# SCH_ZX-WiFi_2024-03-22.net
KiCad netlist of a schematic drawn in EasyEDA
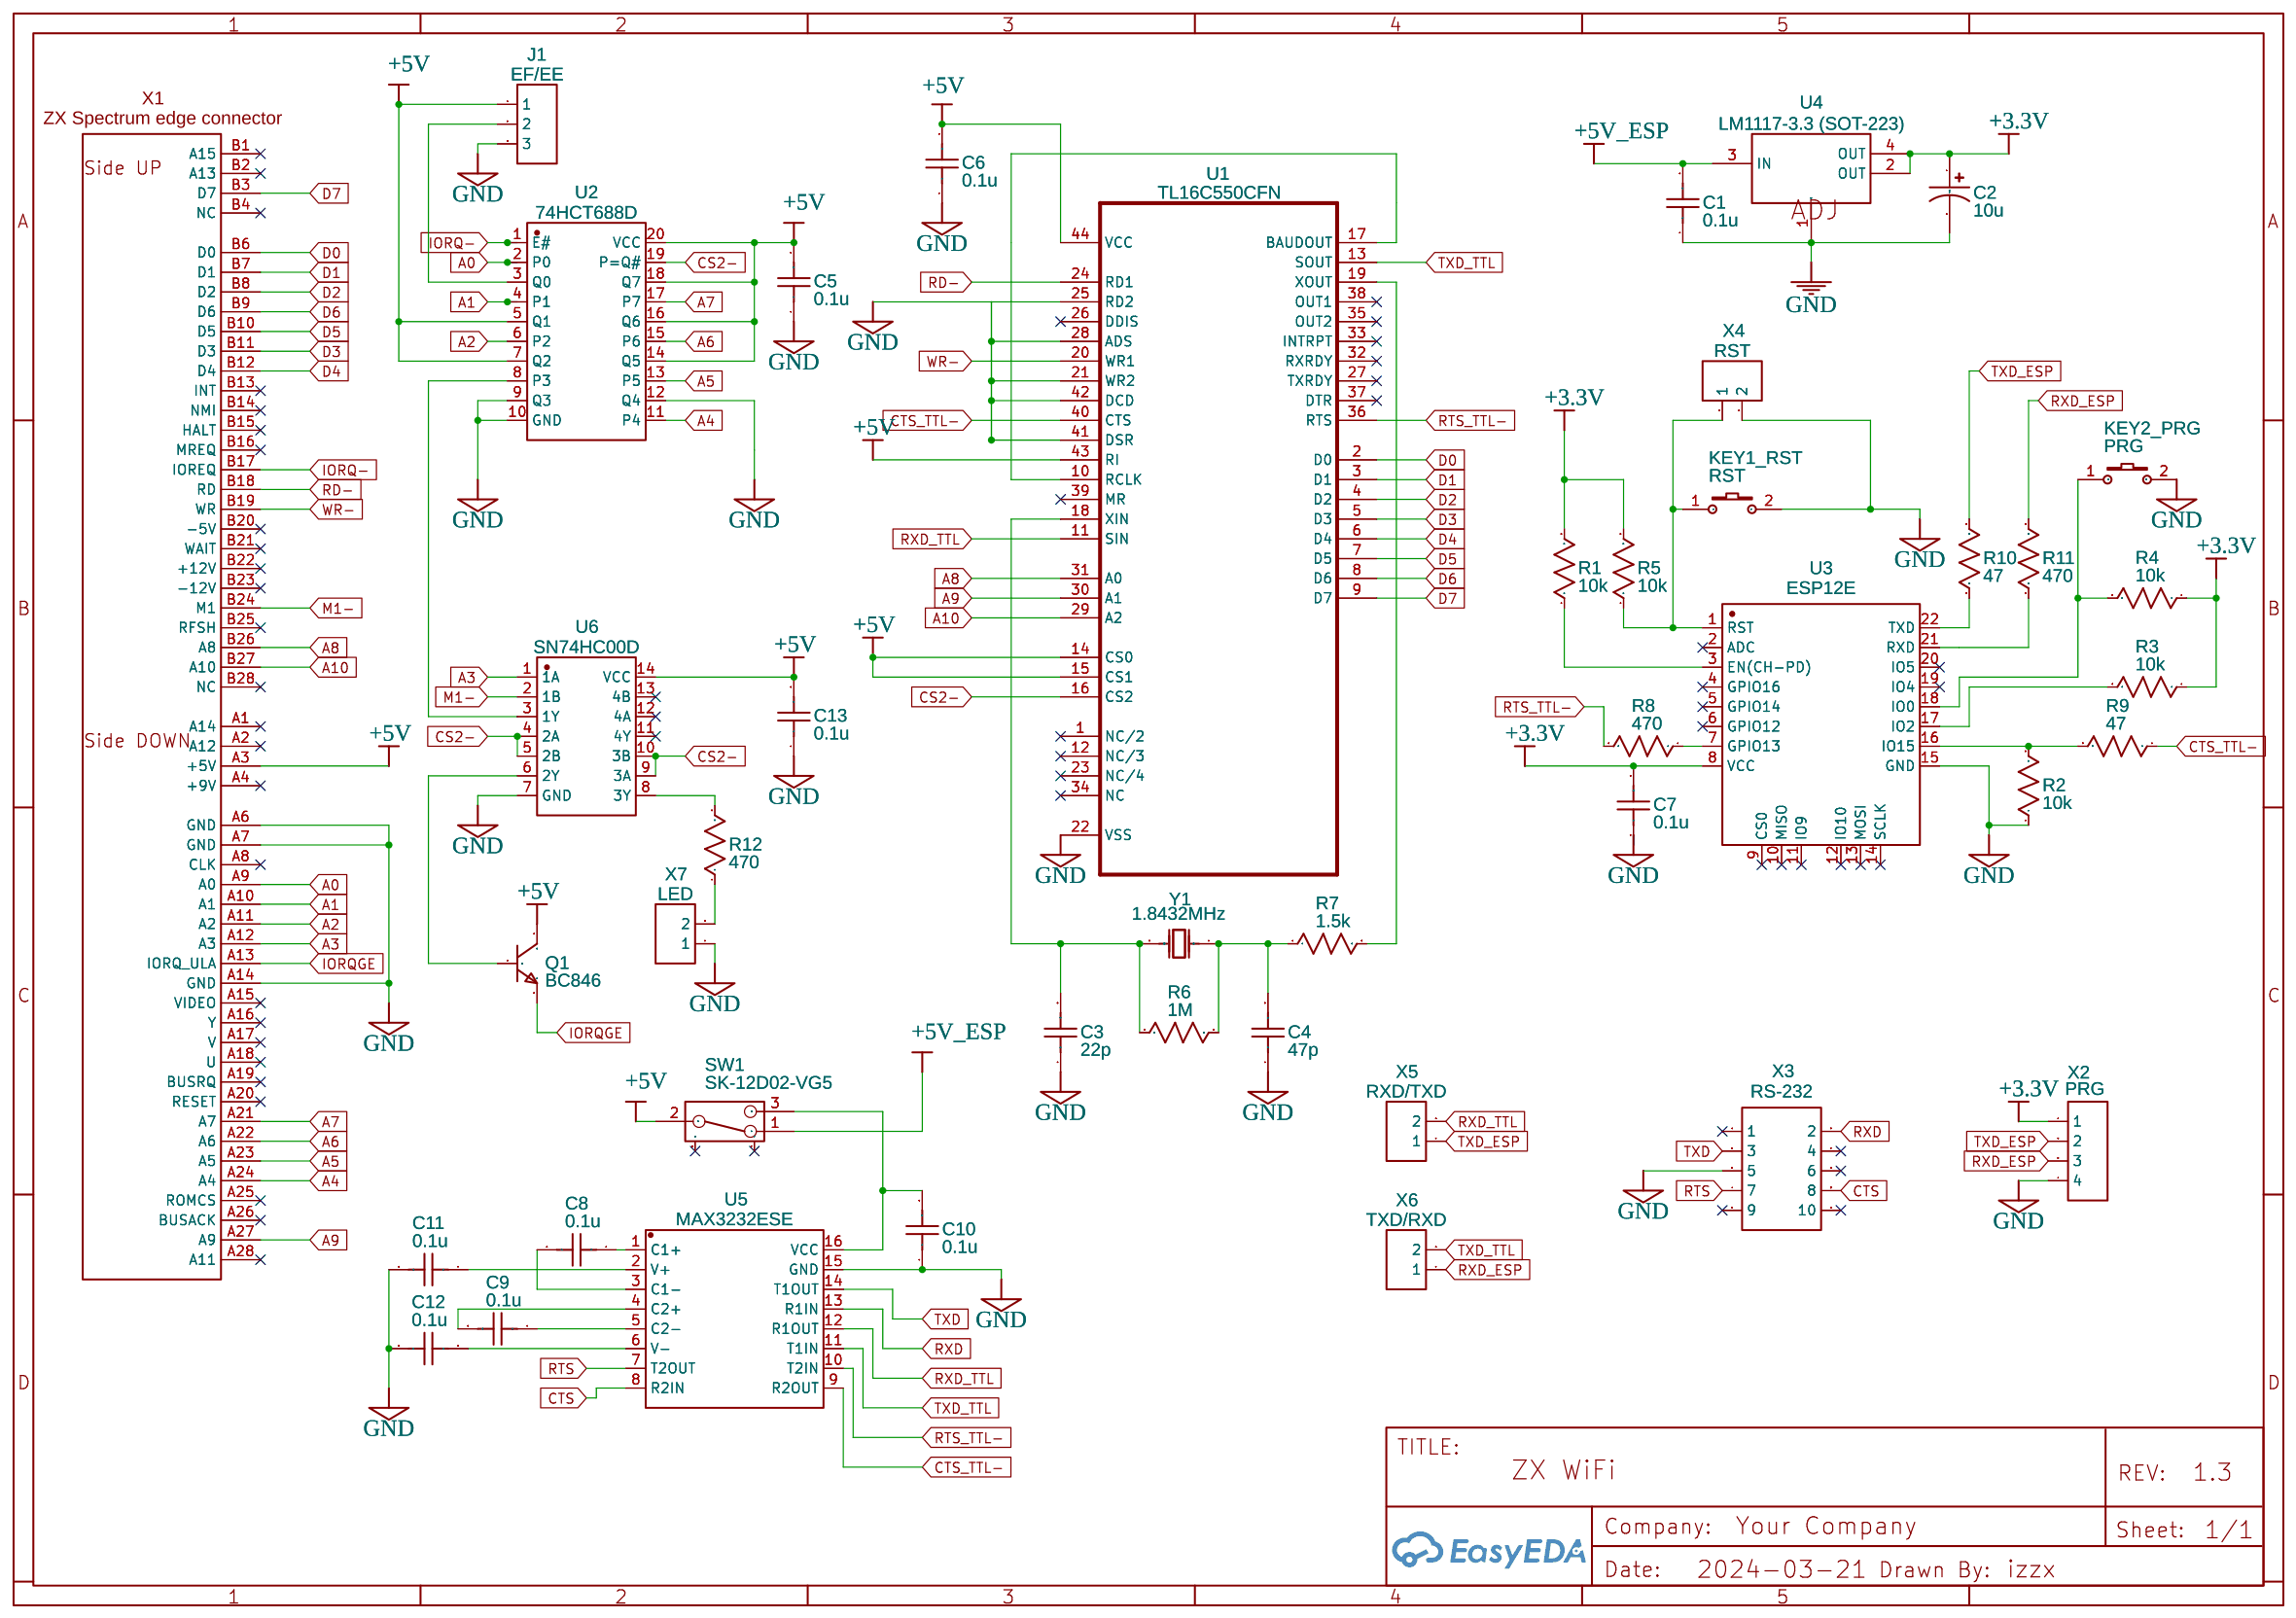
[diagram p0: schematic sheet]

(export (version "E")
  (design (tool "Eeschema 10.0.6"))
  (components
    (comp (ref "C1") (value "0.1u") (libsource (lib "") (part "C_0805_US")))
    (comp (ref "C2") (value "10u") (libsource (lib "") (part "C_Tan_SMD_A_US")))
    (comp (ref "C3") (value "22p") (libsource (lib "") (part "C_0805_US")))
    (comp (ref "C4") (value "47p") (libsource (lib "") (part "C_0805_US")))
    (comp (ref "C5") (value "0.1u") (libsource (lib "") (part "C_0805_US")))
    (comp (ref "C6") (value "0.1u") (libsource (lib "") (part "C_0805_US")))
    (comp (ref "C7") (value "0.1u") (libsource (lib "") (part "C_0805_US")))
    (comp (ref "C8") (value "0.1u") (libsource (lib "") (part "C_0805_US_1")))
    (comp (ref "C9") (value "0.1u") (libsource (lib "") (part "C_0805_US_1")))
    (comp (ref "C10") (value "0.1u") (libsource (lib "") (part "C_0805_US")))
    (comp (ref "C11") (value "0.1u") (libsource (lib "") (part "C_0805_US_1")))
    (comp (ref "C12") (value "0.1u") (libsource (lib "") (part "C_0805_US_1")))
    (comp (ref "C13") (value "0.1u") (libsource (lib "") (part "C_0805_US")))
    (comp (ref "J1") (value "EF/EE") (libsource (lib "") (part "HDR-M-2.54_1x3")))
    (comp (ref "KEY1_RST")
      (value "RST")
      (fields (field (name "Manufacturer Part") "K2-1107ST-A4SW-06"))
      (libsource (lib "") (part "K2-3.6×6.1_SMD_1"))
    )
    (comp (ref "KEY2_PRG")
      (value "PRG")
      (fields (field (name "Manufacturer Part") "K2-1107ST-A4SW-06"))
      (libsource (lib "") (part "K2-3.6×6.1_SMD"))
    )
    (comp (ref "Q1")
      (value "BC846")
      (fields (field (name "Manufacturer Part") "BC846A") (field (name "Manufacturer") "CJ(江苏长电/长晶)"))
      (libsource (lib "") (part "BC846"))
    )
    (comp (ref "R1") (value "10k") (libsource (lib "") (part "R_0805_US_1")))
    (comp (ref "R2") (value "10k") (libsource (lib "") (part "R_0805_US_1")))
    (comp (ref "R3") (value "10k") (libsource (lib "") (part "R_0805_US")))
    (comp (ref "R4") (value "10k") (libsource (lib "") (part "R_0805_US")))
    (comp (ref "R5") (value "10k") (libsource (lib "") (part "R_0805_US_1")))
    (comp (ref "R6") (value "1M") (libsource (lib "") (part "R_0805_US_2")))
    (comp (ref "R7") (value "1.5k") (libsource (lib "") (part "R_0805_US_2")))
    (comp (ref "R8") (value "470") (libsource (lib "") (part "R_0805_US")))
    (comp (ref "R9") (value "47") (libsource (lib "") (part "R_0805_US")))
    (comp (ref "R10") (value "47") (libsource (lib "") (part "R_0805_US_1")))
    (comp (ref "R11") (value "470") (libsource (lib "") (part "R_0805_US_1")))
    (comp (ref "R12") (value "470") (libsource (lib "") (part "R_0805_US_1")))
    (comp (ref "SW1")
      (value "SK-12D02-VG5")
      (fields (field (name "Manufacturer") "Rectangular Connectors - Contacts"))
      (libsource (lib "") (part "SK-12D02-VG5"))
    )
    (comp (ref "U1") (value "TL16C550CFN") (libsource (lib "") (part "TL16C550CFN")))
    (comp (ref "U2")
      (value "74HCT688D")
      (fields (field (name "Manufacturer") "PHILIPS"))
      (libsource (lib "") (part "74HCT688D"))
    )
    (comp (ref "U3") (value "ESP12E") (libsource (lib "") (part "ESP12E/F")))
    (comp (ref "U4")
      (value "LM1117-3.3 (SOT-223)")
      (fields (field (name "Manufacturer Part") "LM317G-AA3-R") (field (name "Manufacturer") "UTC"))
      (libsource (lib "") (part "LM317(SOT-223)"))
    )
    (comp (ref "U5")
      (value "MAX3232ESE")
      (fields (field (name "Manufacturer") "UMW(友台半导体)"))
      (libsource (lib "") (part "MAX3232ESE"))
    )
    (comp (ref "U6")
      (value "SN74HC00D")
      (fields (field (name "Manufacturer") "TI(德州仪器)"))
      (libsource (lib "") (part "SN74HC00D"))
    )
    (comp (ref "X1") (value "ZX SPECTRUM CONNECTOR") (libsource (lib "") (part "ZX SPECTRUM CONNECTOR")))
    (comp (ref "X2") (value "PRG") (libsource (lib "") (part "HDR-M-2.54_1x4")))
    (comp (ref "X3") (value "RS-232") (libsource (lib "") (part "HDR-M-2.54_2x5")))
    (comp (ref "X4") (value "RST") (libsource (lib "") (part "HDR-M-2.54_1x2")))
    (comp (ref "X5") (value "RXD/TXD") (libsource (lib "") (part "HDR-M-2.54_1x2_1")))
    (comp (ref "X6") (value "TXD/RXD") (libsource (lib "") (part "HDR-M-2.54_1x2_1")))
    (comp (ref "X7") (value "LED") (libsource (lib "") (part "HDR-M-2.54_1x2_1")))
    (comp (ref "Y1")
      (value "1.8432MHz")
      (fields (field (name "Manufacturer Part") "X49UD3579MSD2SC") (field (name "Manufacturer") "ValuePro"))
      (libsource (lib "") (part "X49UD3579MSD2SC"))
    )
  )
  (nets
    (net (code "1") (name "+3.3V") (class "Default")
      (node (ref "C2") (pin "1") (pinfunction "1_1") (pintype "unspecified"))
      (node (ref "C7") (pin "2") (pinfunction "2_2") (pintype "unspecified"))
      (node (ref "R1") (pin "2") (pinfunction "2_2") (pintype "unspecified"))
      (node (ref "R3") (pin "1") (pinfunction "1_1") (pintype "unspecified"))
      (node (ref "R4") (pin "1") (pinfunction "1_1") (pintype "unspecified"))
      (node (ref "R5") (pin "2") (pinfunction "2_2") (pintype "unspecified"))
      (node (ref "U3") (pin "8") (pinfunction "VCC_8") (pintype "unspecified"))
      (node (ref "U4") (pin "2") (pinfunction "OUT_2") (pintype "passive"))
      (node (ref "U4") (pin "4") (pinfunction "OUT_4") (pintype "passive"))
      (node (ref "X2") (pin "1") (pinfunction "1_1") (pintype "unspecified"))
    )
    (net (code "2") (name "+5V") (class "Default")
      (node (ref "C13") (pin "2") (pinfunction "2_2") (pintype "unspecified"))
      (node (ref "C5") (pin "2") (pinfunction "2_2") (pintype "unspecified"))
      (node (ref "C6") (pin "2") (pinfunction "2_2") (pintype "unspecified"))
      (node (ref "J1") (pin "1") (pinfunction "1_1") (pintype "input"))
      (node (ref "Q1") (pin "3") (pinfunction "C_3") (pintype "unspecified"))
      (node (ref "SW1") (pin "2") (pinfunction "2_2") (pintype "unspecified"))
      (node (ref "U1") (pin "14") (pinfunction "CS0_14") (pintype "input"))
      (node (ref "U1") (pin "15") (pinfunction "CS1_15") (pintype "input"))
      (node (ref "U1") (pin "43") (pinfunction "RI_43") (pintype "input"))
      (node (ref "U1") (pin "44") (pinfunction "VCC_44") (pintype "passive"))
      (node (ref "U2") (pin "14") (pinfunction "Q5_14") (pintype "unspecified"))
      (node (ref "U2") (pin "16") (pinfunction "Q6_16") (pintype "unspecified"))
      (node (ref "U2") (pin "18") (pinfunction "Q7_18") (pintype "unspecified"))
      (node (ref "U2") (pin "20") (pinfunction "VCC_20") (pintype "unspecified"))
      (node (ref "U2") (pin "5") (pinfunction "Q1_5") (pintype "unspecified"))
      (node (ref "U2") (pin "7") (pinfunction "Q2_7") (pintype "unspecified"))
      (node (ref "U6") (pin "14") (pinfunction "VCC_14") (pintype "unspecified"))
      (node (ref "X1") (pin "A3") (pinfunction "+5V_A3") (pintype "unspecified"))
    )
    (net (code "3") (name "+5V_ESP") (class "Default")
      (node (ref "C1") (pin "2") (pinfunction "2_2") (pintype "unspecified"))
      (node (ref "SW1") (pin "1") (pinfunction "1_1") (pintype "unspecified"))
      (node (ref "U4") (pin "3") (pinfunction "IN_3") (pintype "passive"))
    )
    (net (code "4") (name "A0") (class "Default")
      (node (ref "U2") (pin "2") (pinfunction "P0_2") (pintype "unspecified"))
      (node (ref "X1") (pin "A9") (pinfunction "A0_A9") (pintype "unspecified"))
    )
    (net (code "5") (name "A1") (class "Default")
      (node (ref "U2") (pin "4") (pinfunction "P1_4") (pintype "unspecified"))
      (node (ref "X1") (pin "A10") (pinfunction "A1_A10") (pintype "unspecified"))
    )
    (net (code "6") (name "A2") (class "Default")
      (node (ref "U2") (pin "6") (pinfunction "P2_6") (pintype "unspecified"))
      (node (ref "X1") (pin "A11") (pinfunction "A2_A11") (pintype "unspecified"))
    )
    (net (code "7") (name "A3") (class "Default")
      (node (ref "U6") (pin "1") (pinfunction "1A_1") (pintype "unspecified"))
      (node (ref "X1") (pin "A12") (pinfunction "A3_A12") (pintype "unspecified"))
    )
    (net (code "8") (name "A4") (class "Default")
      (node (ref "U2") (pin "11") (pinfunction "P4_11") (pintype "unspecified"))
      (node (ref "X1") (pin "A24") (pinfunction "A4_A24") (pintype "unspecified"))
    )
    (net (code "9") (name "A5") (class "Default")
      (node (ref "U2") (pin "13") (pinfunction "P5_13") (pintype "unspecified"))
      (node (ref "X1") (pin "A23") (pinfunction "A5_A23") (pintype "unspecified"))
    )
    (net (code "10") (name "A6") (class "Default")
      (node (ref "U2") (pin "15") (pinfunction "P6_15") (pintype "unspecified"))
      (node (ref "X1") (pin "A22") (pinfunction "A6_A22") (pintype "unspecified"))
    )
    (net (code "11") (name "A7") (class "Default")
      (node (ref "U2") (pin "17") (pinfunction "P7_17") (pintype "unspecified"))
      (node (ref "X1") (pin "A21") (pinfunction "A7_A21") (pintype "unspecified"))
    )
    (net (code "12") (name "A8") (class "Default")
      (node (ref "U1") (pin "31") (pinfunction "A0_31") (pintype "input"))
      (node (ref "X1") (pin "B26") (pinfunction "A8_B26") (pintype "unspecified"))
    )
    (net (code "13") (name "A9") (class "Default")
      (node (ref "U1") (pin "30") (pinfunction "A1_30") (pintype "input"))
      (node (ref "X1") (pin "A27") (pinfunction "A9_A27") (pintype "unspecified"))
    )
    (net (code "14") (name "A10") (class "Default")
      (node (ref "U1") (pin "29") (pinfunction "A2_29") (pintype "input"))
      (node (ref "X1") (pin "B27") (pinfunction "A10_B27") (pintype "unspecified"))
    )
    (net (code "15") (name "CS2-") (class "Default")
      (node (ref "U1") (pin "16") (pinfunction "CS2_16") (pintype "input"))
      (node (ref "U2") (pin "19") (pinfunction "P=Q#_19") (pintype "unspecified"))
      (node (ref "U6") (pin "10") (pinfunction "3B_10") (pintype "unspecified"))
      (node (ref "U6") (pin "4") (pinfunction "2A_4") (pintype "unspecified"))
      (node (ref "U6") (pin "5") (pinfunction "2B_5") (pintype "unspecified"))
      (node (ref "U6") (pin "9") (pinfunction "3A_9") (pintype "unspecified"))
    )
    (net (code "16") (name "CTS") (class "Default")
      (node (ref "U5") (pin "8") (pinfunction "R2IN_8") (pintype "unspecified"))
      (node (ref "X3") (pin "8") (pinfunction "8_8") (pintype "unspecified"))
    )
    (net (code "17") (name "CTS_TTL-") (class "Default")
      (node (ref "R9") (pin "1") (pinfunction "1_1") (pintype "unspecified"))
      (node (ref "U1") (pin "40") (pinfunction "CTS_40") (pintype "input"))
      (node (ref "U5") (pin "9") (pinfunction "R2OUT_9") (pintype "unspecified"))
    )
    (net (code "18") (name "D0") (class "Default")
      (node (ref "U1") (pin "2") (pinfunction "D0_2") (pintype "unspecified"))
      (node (ref "X1") (pin "B6") (pinfunction "D0_B6") (pintype "bidirectional"))
    )
    (net (code "19") (name "D1") (class "Default")
      (node (ref "U1") (pin "3") (pinfunction "D1_3") (pintype "unspecified"))
      (node (ref "X1") (pin "B7") (pinfunction "D1_B7") (pintype "bidirectional"))
    )
    (net (code "20") (name "D2") (class "Default")
      (node (ref "U1") (pin "4") (pinfunction "D2_4") (pintype "unspecified"))
      (node (ref "X1") (pin "B8") (pinfunction "D2_B8") (pintype "bidirectional"))
    )
    (net (code "21") (name "D3") (class "Default")
      (node (ref "U1") (pin "5") (pinfunction "D3_5") (pintype "unspecified"))
      (node (ref "X1") (pin "B11") (pinfunction "D3_B11") (pintype "unspecified"))
    )
    (net (code "22") (name "D4") (class "Default")
      (node (ref "U1") (pin "6") (pinfunction "D4_6") (pintype "unspecified"))
      (node (ref "X1") (pin "B12") (pinfunction "D4_B12") (pintype "unspecified"))
    )
    (net (code "23") (name "D5") (class "Default")
      (node (ref "U1") (pin "7") (pinfunction "D5_7") (pintype "unspecified"))
      (node (ref "X1") (pin "B10") (pinfunction "D5_B10") (pintype "bidirectional"))
    )
    (net (code "24") (name "D6") (class "Default")
      (node (ref "U1") (pin "8") (pinfunction "D6_8") (pintype "unspecified"))
      (node (ref "X1") (pin "B9") (pinfunction "D6_B9") (pintype "unspecified"))
    )
    (net (code "25") (name "D7") (class "Default")
      (node (ref "U1") (pin "9") (pinfunction "D7_9") (pintype "unspecified"))
      (node (ref "X1") (pin "B3") (pinfunction "D7_B3") (pintype "bidirectional"))
    )
    (net (code "26") (name "GND") (class "Default")
      (node (ref "C1") (pin "1") (pinfunction "1_1") (pintype "unspecified"))
      (node (ref "C10") (pin "1") (pinfunction "1_1") (pintype "unspecified"))
      (node (ref "C11") (pin "2") (pinfunction "2_2") (pintype "unspecified"))
      (node (ref "C12") (pin "2") (pinfunction "2_2") (pintype "unspecified"))
      (node (ref "C13") (pin "1") (pinfunction "1_1") (pintype "unspecified"))
      (node (ref "C2") (pin "2") (pinfunction "2_2") (pintype "unspecified"))
      (node (ref "C3") (pin "1") (pinfunction "1_1") (pintype "unspecified"))
      (node (ref "C4") (pin "1") (pinfunction "1_1") (pintype "unspecified"))
      (node (ref "C5") (pin "1") (pinfunction "1_1") (pintype "unspecified"))
      (node (ref "C6") (pin "1") (pinfunction "1_1") (pintype "unspecified"))
      (node (ref "C7") (pin "1") (pinfunction "1_1") (pintype "unspecified"))
      (node (ref "J1") (pin "3") (pinfunction "3_3") (pintype "input"))
      (node (ref "KEY1_RST") (pin "2") (pinfunction "2_2") (pintype "unspecified"))
      (node (ref "KEY2_PRG") (pin "2") (pinfunction "2_2") (pintype "unspecified"))
      (node (ref "R2") (pin "1") (pinfunction "1_1") (pintype "unspecified"))
      (node (ref "U1") (pin "21") (pinfunction "WR2_21") (pintype "input"))
      (node (ref "U1") (pin "22") (pinfunction "VSS_22") (pintype "passive"))
      (node (ref "U1") (pin "25") (pinfunction "RD2_25") (pintype "input"))
      (node (ref "U1") (pin "28") (pinfunction "ADS_28") (pintype "input"))
      (node (ref "U1") (pin "41") (pinfunction "DSR_41") (pintype "input"))
      (node (ref "U1") (pin "42") (pinfunction "DCD_42") (pintype "input"))
      (node (ref "U2") (pin "10") (pinfunction "GND_10") (pintype "unspecified"))
      (node (ref "U2") (pin "12") (pinfunction "Q4_12") (pintype "unspecified"))
      (node (ref "U2") (pin "9") (pinfunction "Q3_9") (pintype "unspecified"))
      (node (ref "U3") (pin "15") (pinfunction "GND_15") (pintype "unspecified"))
      (node (ref "U4") (pin "1") (pinfunction "ADJ_1") (pintype "passive"))
      (node (ref "U5") (pin "15") (pinfunction "GND_15") (pintype "unspecified"))
      (node (ref "U6") (pin "7") (pinfunction "GND_7") (pintype "unspecified"))
      (node (ref "X1") (pin "A14") (pinfunction "GND_A14") (pintype "unspecified"))
      (node (ref "X1") (pin "A6") (pinfunction "GND_A6") (pintype "unspecified"))
      (node (ref "X1") (pin "A7") (pinfunction "GND_A7") (pintype "unspecified"))
      (node (ref "X2") (pin "4") (pinfunction "4_4") (pintype "unspecified"))
      (node (ref "X3") (pin "5") (pinfunction "5_5") (pintype "unspecified"))
      (node (ref "X4") (pin "2") (pinfunction "2_2") (pintype "unspecified"))
      (node (ref "X7") (pin "1") (pinfunction "1_1") (pintype "unspecified"))
    )
    (net (code "27") (name "IORQ-") (class "Default")
      (node (ref "U2") (pin "1") (pinfunction "E#_1") (pintype "unspecified"))
      (node (ref "X1") (pin "B17") (pinfunction "IOREQ_B17") (pintype "unspecified"))
    )
    (net (code "28") (name "IORQGE") (class "Default")
      (node (ref "Q1") (pin "2") (pinfunction "E_2") (pintype "unspecified"))
      (node (ref "X1") (pin "A13") (pinfunction "IORQ_ULA_A13") (pintype "unspecified"))
    )
    (net (code "29") (name "M1-") (class "Default")
      (node (ref "U6") (pin "2") (pinfunction "1B_2") (pintype "unspecified"))
      (node (ref "X1") (pin "B24") (pinfunction "M1_B24") (pintype "unspecified"))
    )
    (net (code "30") (name "Net-(Q1-B)") (class "Default")
      (node (ref "Q1") (pin "1") (pinfunction "B_1") (pintype "unspecified"))
      (node (ref "U6") (pin "6") (pinfunction "2Y_6") (pintype "unspecified"))
    )
    (net (code "31") (name "Net-(R12-Pad1)") (class "Default")
      (node (ref "R12") (pin "1") (pinfunction "1_1") (pintype "unspecified"))
      (node (ref "X7") (pin "2") (pinfunction "2_2") (pintype "unspecified"))
    )
    (net (code "32") (name "Net-(U1-BAUDOUT)") (class "Default")
      (node (ref "U1") (pin "10") (pinfunction "RCLK_10") (pintype "input"))
      (node (ref "U1") (pin "17") (pinfunction "BAUDOUT_17") (pintype "output"))
    )
    (net (code "33") (name "Net-(U1-XIN)") (class "Default")
      (node (ref "C3") (pin "2") (pinfunction "2_2") (pintype "unspecified"))
      (node (ref "R6") (pin "1") (pinfunction "1_1") (pintype "unspecified"))
      (node (ref "U1") (pin "18") (pinfunction "XIN_18") (pintype "input"))
      (node (ref "Y1") (pin "2") (pinfunction "OSC2_2") (pintype "input"))
    )
    (net (code "34") (name "Net-(U1-XOUT)") (class "Default")
      (node (ref "R7") (pin "2") (pinfunction "2_2") (pintype "unspecified"))
      (node (ref "U1") (pin "19") (pinfunction "XOUT_19") (pintype "output"))
    )
    (net (code "35") (name "Net-(U2-P3)") (class "Default")
      (node (ref "U2") (pin "8") (pinfunction "P3_8") (pintype "unspecified"))
      (node (ref "U6") (pin "3") (pinfunction "1Y_3") (pintype "unspecified"))
    )
    (net (code "36") (name "Net-(U2-Q0)") (class "Default")
      (node (ref "J1") (pin "2") (pinfunction "2_2") (pintype "input"))
      (node (ref "U2") (pin "3") (pinfunction "Q0_3") (pintype "unspecified"))
    )
    (net (code "37") (name "Net-(U3-EN(CH-PD))") (class "Default")
      (node (ref "R1") (pin "1") (pinfunction "1_1") (pintype "unspecified"))
      (node (ref "U3") (pin "3") (pinfunction "EN(CH-PD)_3") (pintype "unspecified"))
    )
    (net (code "38") (name "Net-(U3-GPIO13)") (class "Default")
      (node (ref "R8") (pin "1") (pinfunction "1_1") (pintype "unspecified"))
      (node (ref "U3") (pin "7") (pinfunction "GPIO13_7") (pintype "unspecified"))
    )
    (net (code "39") (name "Net-(U3-IO0)") (class "Default")
      (node (ref "KEY2_PRG") (pin "1") (pinfunction "1_1") (pintype "unspecified"))
      (node (ref "R4") (pin "2") (pinfunction "2_2") (pintype "unspecified"))
      (node (ref "U3") (pin "18") (pinfunction "IO0_18") (pintype "unspecified"))
    )
    (net (code "40") (name "Net-(U3-IO2)") (class "Default")
      (node (ref "R3") (pin "2") (pinfunction "2_2") (pintype "unspecified"))
      (node (ref "U3") (pin "17") (pinfunction "IO2_17") (pintype "unspecified"))
    )
    (net (code "41") (name "Net-(U3-IO15)") (class "Default")
      (node (ref "R2") (pin "2") (pinfunction "2_2") (pintype "unspecified"))
      (node (ref "R9") (pin "2") (pinfunction "2_2") (pintype "unspecified"))
      (node (ref "U3") (pin "16") (pinfunction "IO15_16") (pintype "unspecified"))
    )
    (net (code "42") (name "Net-(U3-RST)") (class "Default")
      (node (ref "KEY1_RST") (pin "1") (pinfunction "1_1") (pintype "unspecified"))
      (node (ref "R5") (pin "1") (pinfunction "1_1") (pintype "unspecified"))
      (node (ref "U3") (pin "1") (pinfunction "RST_1") (pintype "unspecified"))
      (node (ref "X4") (pin "1") (pinfunction "1_1") (pintype "unspecified"))
    )
    (net (code "43") (name "Net-(U3-RXD)") (class "Default")
      (node (ref "R11") (pin "1") (pinfunction "1_1") (pintype "unspecified"))
      (node (ref "U3") (pin "21") (pinfunction "RXD_21") (pintype "unspecified"))
    )
    (net (code "44") (name "Net-(U3-TXD)") (class "Default")
      (node (ref "R10") (pin "1") (pinfunction "1_1") (pintype "unspecified"))
      (node (ref "U3") (pin "22") (pinfunction "TXD_22") (pintype "unspecified"))
    )
    (net (code "45") (name "Net-(U5-C1+)") (class "Default")
      (node (ref "C8") (pin "1") (pinfunction "1_1") (pintype "unspecified"))
      (node (ref "U5") (pin "1") (pinfunction "C1+_1") (pintype "unspecified"))
    )
    (net (code "46") (name "Net-(U5-C1-)") (class "Default")
      (node (ref "C8") (pin "2") (pinfunction "2_2") (pintype "unspecified"))
      (node (ref "U5") (pin "3") (pinfunction "C1-_3") (pintype "unspecified"))
    )
    (net (code "47") (name "Net-(U5-C2+)") (class "Default")
      (node (ref "C9") (pin "2") (pinfunction "2_2") (pintype "unspecified"))
      (node (ref "U5") (pin "4") (pinfunction "C2+_4") (pintype "unspecified"))
    )
    (net (code "48") (name "Net-(U5-C2-)") (class "Default")
      (node (ref "C9") (pin "1") (pinfunction "1_1") (pintype "unspecified"))
      (node (ref "U5") (pin "5") (pinfunction "C2-_5") (pintype "unspecified"))
    )
    (net (code "49") (name "Net-(U5-V+)") (class "Default")
      (node (ref "C11") (pin "1") (pinfunction "1_1") (pintype "unspecified"))
      (node (ref "U5") (pin "2") (pinfunction "V+_2") (pintype "unspecified"))
    )
    (net (code "50") (name "Net-(U5-V-)") (class "Default")
      (node (ref "C12") (pin "1") (pinfunction "1_1") (pintype "unspecified"))
      (node (ref "U5") (pin "6") (pinfunction "V-_6") (pintype "unspecified"))
    )
    (net (code "51") (name "Net-(U5-VCC)") (class "Default")
      (node (ref "C10") (pin "2") (pinfunction "2_2") (pintype "unspecified"))
      (node (ref "SW1") (pin "3") (pinfunction "3_3") (pintype "unspecified"))
      (node (ref "U5") (pin "16") (pinfunction "VCC_16") (pintype "unspecified"))
    )
    (net (code "52") (name "Net-(U6-3Y)") (class "Default")
      (node (ref "R12") (pin "2") (pinfunction "2_2") (pintype "unspecified"))
      (node (ref "U6") (pin "8") (pinfunction "3Y_8") (pintype "unspecified"))
    )
    (net (code "53") (name "Net-(Y1-OSC1)") (class "Default")
      (node (ref "C4") (pin "2") (pinfunction "2_2") (pintype "unspecified"))
      (node (ref "R6") (pin "2") (pinfunction "2_2") (pintype "unspecified"))
      (node (ref "R7") (pin "1") (pinfunction "1_1") (pintype "unspecified"))
      (node (ref "Y1") (pin "1") (pinfunction "OSC1_1") (pintype "input"))
    )
    (net (code "54") (name "RD-") (class "Default")
      (node (ref "U1") (pin "24") (pinfunction "RD1_24") (pintype "input"))
      (node (ref "X1") (pin "B18") (pinfunction "RD_B18") (pintype "unspecified"))
    )
    (net (code "55") (name "RTS") (class "Default")
      (node (ref "U5") (pin "7") (pinfunction "T2OUT_7") (pintype "unspecified"))
      (node (ref "X3") (pin "7") (pinfunction "7_7") (pintype "unspecified"))
    )
    (net (code "56") (name "RTS_TTL-") (class "Default")
      (node (ref "R8") (pin "2") (pinfunction "2_2") (pintype "unspecified"))
      (node (ref "U1") (pin "36") (pinfunction "RTS_36") (pintype "output"))
      (node (ref "U5") (pin "10") (pinfunction "T2IN_10") (pintype "unspecified"))
    )
    (net (code "57") (name "RXD") (class "Default")
      (node (ref "U5") (pin "13") (pinfunction "R1IN_13") (pintype "unspecified"))
      (node (ref "X3") (pin "2") (pinfunction "2_2") (pintype "unspecified"))
    )
    (net (code "58") (name "RXD_ESP") (class "Default")
      (node (ref "R11") (pin "2") (pinfunction "2_2") (pintype "unspecified"))
      (node (ref "X2") (pin "3") (pinfunction "3_3") (pintype "unspecified"))
      (node (ref "X6") (pin "1") (pinfunction "1_1") (pintype "unspecified"))
    )
    (net (code "59") (name "RXD_TTL") (class "Default")
      (node (ref "U1") (pin "11") (pinfunction "SIN_11") (pintype "input"))
      (node (ref "U5") (pin "12") (pinfunction "R1OUT_12") (pintype "unspecified"))
      (node (ref "X5") (pin "2") (pinfunction "2_2") (pintype "unspecified"))
    )
    (net (code "60") (name "TXD") (class "Default")
      (node (ref "U5") (pin "14") (pinfunction "T1OUT_14") (pintype "unspecified"))
      (node (ref "X3") (pin "3") (pinfunction "3_3") (pintype "unspecified"))
    )
    (net (code "61") (name "TXD_ESP") (class "Default")
      (node (ref "R10") (pin "2") (pinfunction "2_2") (pintype "unspecified"))
      (node (ref "X2") (pin "2") (pinfunction "2_2") (pintype "unspecified"))
      (node (ref "X5") (pin "1") (pinfunction "1_1") (pintype "unspecified"))
    )
    (net (code "62") (name "TXD_TTL") (class "Default")
      (node (ref "U1") (pin "13") (pinfunction "SOUT_13") (pintype "output"))
      (node (ref "U5") (pin "11") (pinfunction "T1IN_11") (pintype "unspecified"))
      (node (ref "X6") (pin "2") (pinfunction "2_2") (pintype "unspecified"))
    )
    (net (code "63") (name "WR-") (class "Default")
      (node (ref "U1") (pin "20") (pinfunction "WR1_20") (pintype "input"))
      (node (ref "X1") (pin "B19") (pinfunction "WR_B19") (pintype "unspecified"))
    )
    (net (code "64") (name "unconnected-(SW1-Pad4)") (class "Default")
      (node (ref "SW1") (pin "4") (pinfunction "4_4") (pintype "unspecified+no_connect"))
    )
    (net (code "65") (name "unconnected-(SW1-Pad5)") (class "Default")
      (node (ref "SW1") (pin "5") (pinfunction "5_5") (pintype "unspecified+no_connect"))
    )
    (net (code "66") (name "unconnected-(U1-DDIS-Pad26)") (class "Default")
      (node (ref "U1") (pin "26") (pinfunction "DDIS_26") (pintype "input+no_connect"))
    )
    (net (code "67") (name "unconnected-(U1-DTR-Pad37)") (class "Default")
      (node (ref "U1") (pin "37") (pinfunction "DTR_37") (pintype "output+no_connect"))
    )
    (net (code "68") (name "unconnected-(U1-INTRPT-Pad33)") (class "Default")
      (node (ref "U1") (pin "33") (pinfunction "INTRPT_33") (pintype "output+no_connect"))
    )
    (net (code "69") (name "unconnected-(U1-MR-Pad39)") (class "Default")
      (node (ref "U1") (pin "39") (pinfunction "MR_39") (pintype "input+no_connect"))
    )
    (net (code "70") (name "unconnected-(U1-NC-Pad34)") (class "Default")
      (node (ref "U1") (pin "34") (pinfunction "NC_34") (pintype "unspecified+no_connect"))
    )
    (net (code "71") (name "unconnected-(U1-NC{slash}2-Pad1)") (class "Default")
      (node (ref "U1") (pin "1") (pinfunction "NC/2_1") (pintype "unspecified+no_connect"))
    )
    (net (code "72") (name "unconnected-(U1-NC{slash}3-Pad12)") (class "Default")
      (node (ref "U1") (pin "12") (pinfunction "NC/3_12") (pintype "unspecified+no_connect"))
    )
    (net (code "73") (name "unconnected-(U1-NC{slash}4-Pad23)") (class "Default")
      (node (ref "U1") (pin "23") (pinfunction "NC/4_23") (pintype "unspecified+no_connect"))
    )
    (net (code "74") (name "unconnected-(U1-OUT1-Pad38)") (class "Default")
      (node (ref "U1") (pin "38") (pinfunction "OUT1_38") (pintype "output+no_connect"))
    )
    (net (code "75") (name "unconnected-(U1-OUT2-Pad35)") (class "Default")
      (node (ref "U1") (pin "35") (pinfunction "OUT2_35") (pintype "output+no_connect"))
    )
    (net (code "76") (name "unconnected-(U1-RXRDY-Pad32)") (class "Default")
      (node (ref "U1") (pin "32") (pinfunction "RXRDY_32") (pintype "output+no_connect"))
    )
    (net (code "77") (name "unconnected-(U1-TXRDY-Pad27)") (class "Default")
      (node (ref "U1") (pin "27") (pinfunction "TXRDY_27") (pintype "output+no_connect"))
    )
    (net (code "78") (name "unconnected-(U3-ADC-Pad2)") (class "Default")
      (node (ref "U3") (pin "2") (pinfunction "ADC_2") (pintype "unspecified+no_connect"))
    )
    (net (code "79") (name "unconnected-(U3-CS0-Pad9)") (class "Default")
      (node (ref "U3") (pin "9") (pinfunction "CS0_9") (pintype "unspecified+no_connect"))
    )
    (net (code "80") (name "unconnected-(U3-GPIO12-Pad6)") (class "Default")
      (node (ref "U3") (pin "6") (pinfunction "GPIO12_6") (pintype "unspecified+no_connect"))
    )
    (net (code "81") (name "unconnected-(U3-GPIO14-Pad5)") (class "Default")
      (node (ref "U3") (pin "5") (pinfunction "GPIO14_5") (pintype "unspecified+no_connect"))
    )
    (net (code "82") (name "unconnected-(U3-GPIO16-Pad4)") (class "Default")
      (node (ref "U3") (pin "4") (pinfunction "GPIO16_4") (pintype "unspecified+no_connect"))
    )
    (net (code "83") (name "unconnected-(U3-IO4-Pad19)") (class "Default")
      (node (ref "U3") (pin "19") (pinfunction "IO4_19") (pintype "unspecified+no_connect"))
    )
    (net (code "84") (name "unconnected-(U3-IO5-Pad20)") (class "Default")
      (node (ref "U3") (pin "20") (pinfunction "IO5_20") (pintype "unspecified+no_connect"))
    )
    (net (code "85") (name "unconnected-(U3-IO9-Pad11)") (class "Default")
      (node (ref "U3") (pin "11") (pinfunction "IO9_11") (pintype "unspecified+no_connect"))
    )
    (net (code "86") (name "unconnected-(U3-IO10-Pad12)") (class "Default")
      (node (ref "U3") (pin "12") (pinfunction "IO10_12") (pintype "unspecified+no_connect"))
    )
    (net (code "87") (name "unconnected-(U3-MISO-Pad10)") (class "Default")
      (node (ref "U3") (pin "10") (pinfunction "MISO_10") (pintype "unspecified+no_connect"))
    )
    (net (code "88") (name "unconnected-(U3-MOSI-Pad13)") (class "Default")
      (node (ref "U3") (pin "13") (pinfunction "MOSI_13") (pintype "unspecified+no_connect"))
    )
    (net (code "89") (name "unconnected-(U3-SCLK-Pad14)") (class "Default")
      (node (ref "U3") (pin "14") (pinfunction "SCLK_14") (pintype "unspecified+no_connect"))
    )
    (net (code "90") (name "unconnected-(U6-4A-Pad12)") (class "Default")
      (node (ref "U6") (pin "12") (pinfunction "4A_12") (pintype "unspecified+no_connect"))
    )
    (net (code "91") (name "unconnected-(U6-4B-Pad13)") (class "Default")
      (node (ref "U6") (pin "13") (pinfunction "4B_13") (pintype "unspecified+no_connect"))
    )
    (net (code "92") (name "unconnected-(U6-4Y-Pad11)") (class "Default")
      (node (ref "U6") (pin "11") (pinfunction "4Y_11") (pintype "unspecified+no_connect"))
    )
    (net (code "93") (name "unconnected-(X1-+9V-PadA4)") (class "Default")
      (node (ref "X1") (pin "A4") (pinfunction "+9V_A4") (pintype "unspecified+no_connect"))
    )
    (net (code "94") (name "unconnected-(X1-+12V-PadB22)") (class "Default")
      (node (ref "X1") (pin "B22") (pinfunction "+12V_B22") (pintype "unspecified+no_connect"))
    )
    (net (code "95") (name "unconnected-(X1--5V-PadB20)") (class "Default")
      (node (ref "X1") (pin "B20") (pinfunction "-5V_B20") (pintype "unspecified+no_connect"))
    )
    (net (code "96") (name "unconnected-(X1--12V-PadB23)") (class "Default")
      (node (ref "X1") (pin "B23") (pinfunction "-12V_B23") (pintype "unspecified+no_connect"))
    )
    (net (code "97") (name "unconnected-(X1-A11-PadA28)") (class "Default")
      (node (ref "X1") (pin "A28") (pinfunction "A11_A28") (pintype "unspecified+no_connect"))
    )
    (net (code "98") (name "unconnected-(X1-A12-PadA2)") (class "Default")
      (node (ref "X1") (pin "A2") (pinfunction "A12_A2") (pintype "unspecified+no_connect"))
    )
    (net (code "99") (name "unconnected-(X1-A13-PadB2)") (class "Default")
      (node (ref "X1") (pin "B2") (pinfunction "A13_B2") (pintype "output+no_connect"))
    )
    (net (code "100") (name "unconnected-(X1-A14-PadA1)") (class "Default")
      (node (ref "X1") (pin "A1") (pinfunction "A14_A1") (pintype "unspecified+no_connect"))
    )
    (net (code "101") (name "unconnected-(X1-A15-PadB1)") (class "Default")
      (node (ref "X1") (pin "B1") (pinfunction "A15_B1") (pintype "output+no_connect"))
    )
    (net (code "102") (name "unconnected-(X1-BUSACK-PadA26)") (class "Default")
      (node (ref "X1") (pin "A26") (pinfunction "BUSACK_A26") (pintype "unspecified+no_connect"))
    )
    (net (code "103") (name "unconnected-(X1-BUSRQ-PadA19)") (class "Default")
      (node (ref "X1") (pin "A19") (pinfunction "BUSRQ_A19") (pintype "unspecified+no_connect"))
    )
    (net (code "104") (name "unconnected-(X1-CLK-PadA8)") (class "Default")
      (node (ref "X1") (pin "A8") (pinfunction "CLK_A8") (pintype "unspecified+no_connect"))
    )
    (net (code "105") (name "unconnected-(X1-HALT-PadB15)") (class "Default")
      (node (ref "X1") (pin "B15") (pinfunction "HALT_B15") (pintype "unspecified+no_connect"))
    )
    (net (code "106") (name "unconnected-(X1-INT-PadB13)") (class "Default")
      (node (ref "X1") (pin "B13") (pinfunction "INT_B13") (pintype "unspecified+no_connect"))
    )
    (net (code "107") (name "unconnected-(X1-MREQ-PadB16)") (class "Default")
      (node (ref "X1") (pin "B16") (pinfunction "MREQ_B16") (pintype "unspecified+no_connect"))
    )
    (net (code "108") (name "unconnected-(X1-NC-PadB4)") (class "Default")
      (node (ref "X1") (pin "B4") (pinfunction "NC_B4") (pintype "unspecified+no_connect"))
    )
    (net (code "109") (name "unconnected-(X1-NC-PadB28)") (class "Default")
      (node (ref "X1") (pin "B28") (pinfunction "NC_B28") (pintype "unspecified+no_connect"))
    )
    (net (code "110") (name "unconnected-(X1-NMI-PadB14)") (class "Default")
      (node (ref "X1") (pin "B14") (pinfunction "NMI_B14") (pintype "unspecified+no_connect"))
    )
    (net (code "111") (name "unconnected-(X1-RESET-PadA20)") (class "Default")
      (node (ref "X1") (pin "A20") (pinfunction "RESET_A20") (pintype "unspecified+no_connect"))
    )
    (net (code "112") (name "unconnected-(X1-RFSH-PadB25)") (class "Default")
      (node (ref "X1") (pin "B25") (pinfunction "RFSH_B25") (pintype "unspecified+no_connect"))
    )
    (net (code "113") (name "unconnected-(X1-ROMCS-PadA25)") (class "Default")
      (node (ref "X1") (pin "A25") (pinfunction "ROMCS_A25") (pintype "unspecified+no_connect"))
    )
    (net (code "114") (name "unconnected-(X1-U-PadA18)") (class "Default")
      (node (ref "X1") (pin "A18") (pinfunction "U_A18") (pintype "unspecified+no_connect"))
    )
    (net (code "115") (name "unconnected-(X1-V-PadA17)") (class "Default")
      (node (ref "X1") (pin "A17") (pinfunction "V_A17") (pintype "unspecified+no_connect"))
    )
    (net (code "116") (name "unconnected-(X1-VIDEO-PadA15)") (class "Default")
      (node (ref "X1") (pin "A15") (pinfunction "VIDEO_A15") (pintype "unspecified+no_connect"))
    )
    (net (code "117") (name "unconnected-(X1-WAIT-PadB21)") (class "Default")
      (node (ref "X1") (pin "B21") (pinfunction "WAIT_B21") (pintype "unspecified+no_connect"))
    )
    (net (code "118") (name "unconnected-(X1-Y-PadA16)") (class "Default")
      (node (ref "X1") (pin "A16") (pinfunction "Y_A16") (pintype "unspecified+no_connect"))
    )
    (net (code "119") (name "unconnected-(X3-Pad1)") (class "Default")
      (node (ref "X3") (pin "1") (pinfunction "1_1") (pintype "unspecified+no_connect"))
    )
    (net (code "120") (name "unconnected-(X3-Pad4)") (class "Default")
      (node (ref "X3") (pin "4") (pinfunction "4_4") (pintype "unspecified+no_connect"))
    )
    (net (code "121") (name "unconnected-(X3-Pad6)") (class "Default")
      (node (ref "X3") (pin "6") (pinfunction "6_6") (pintype "unspecified+no_connect"))
    )
    (net (code "122") (name "unconnected-(X3-Pad9)") (class "Default")
      (node (ref "X3") (pin "9") (pinfunction "9_9") (pintype "unspecified+no_connect"))
    )
    (net (code "123") (name "unconnected-(X3-Pad10)") (class "Default")
      (node (ref "X3") (pin "10") (pinfunction "10_10") (pintype "unspecified+no_connect"))
    )
  )
)
